# ir.net
KiCad netlist of a schematic drawn in EAGLE
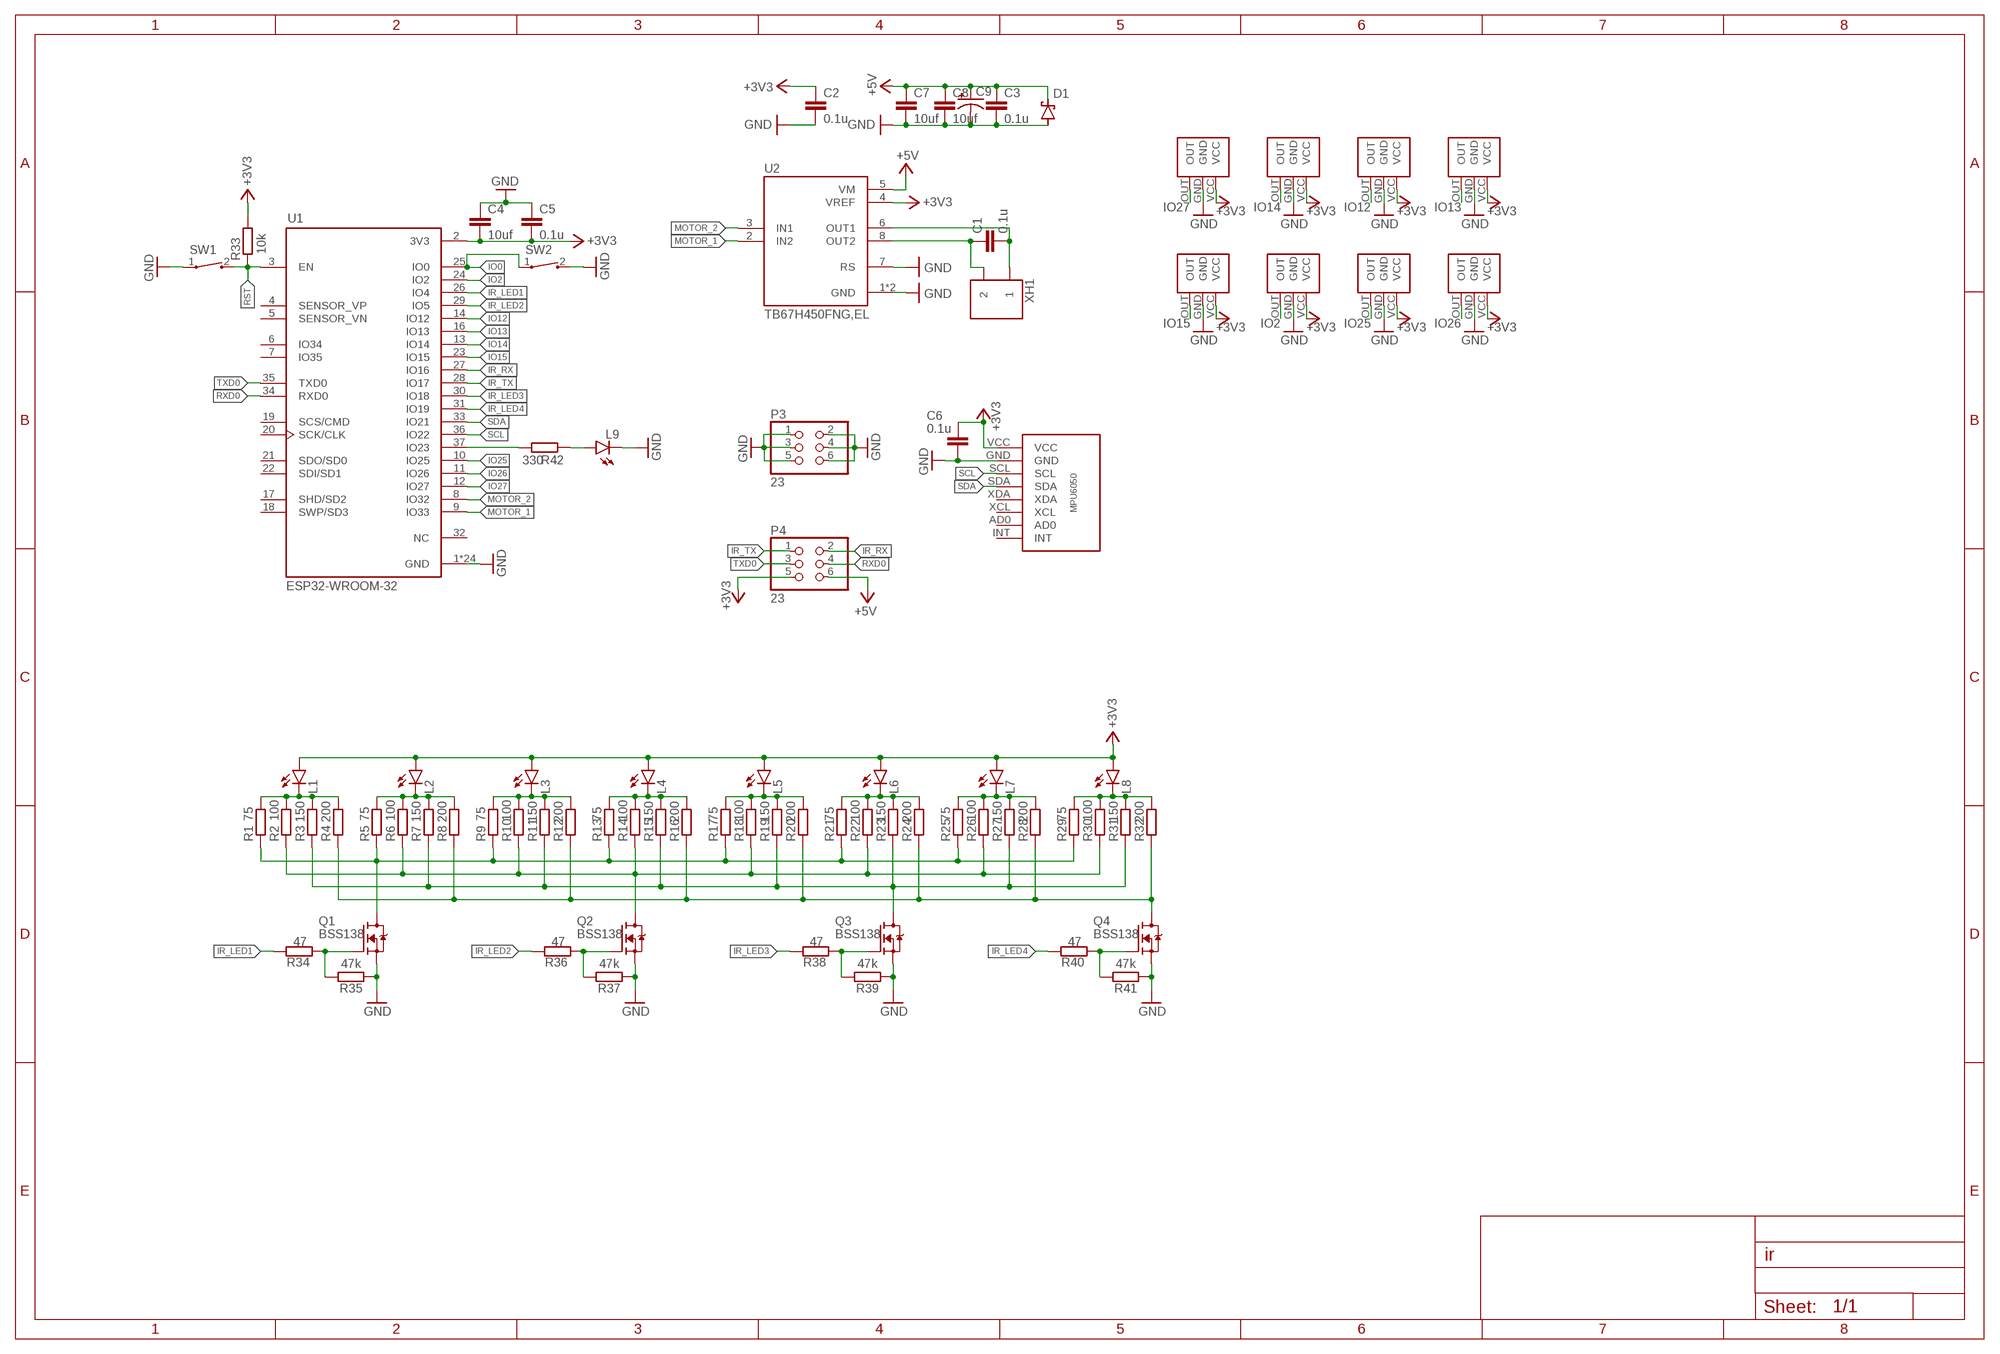
[diagram p0: schematic, sheet 1]

(export (version "E")
  (design (tool "Eeschema 10.0.6"))
  (components
    (comp (ref "C1")
      (value "0.1u")
      (footprint "eagle-import:C0603")
      (libsource (lib "eagle-import") (part "C-EUC0603"))
    )
    (comp (ref "C2")
      (value "0.1u")
      (footprint "eagle-import:C0603")
      (libsource (lib "eagle-import") (part "C-EUC0603"))
    )
    (comp (ref "C3")
      (value "0.1u")
      (footprint "eagle-import:C0603")
      (libsource (lib "eagle-import") (part "C-EUC0603"))
    )
    (comp (ref "C4")
      (value "10uf")
      (footprint "eagle-import:C0805")
      (libsource (lib "eagle-import") (part "C-EUC0805"))
    )
    (comp (ref "C5")
      (value "0.1u")
      (footprint "eagle-import:C0603")
      (libsource (lib "eagle-import") (part "C-EUC0603"))
    )
    (comp (ref "C6")
      (value "0.1u")
      (footprint "eagle-import:C0603")
      (libsource (lib "eagle-import") (part "C-EUC0603"))
    )
    (comp (ref "C7")
      (value "10uf")
      (footprint "eagle-import:C0805")
      (libsource (lib "eagle-import") (part "C-EUC0805"))
    )
    (comp (ref "C8")
      (value "10uf")
      (footprint "eagle-import:C0805")
      (libsource (lib "eagle-import") (part "C-EUC0805"))
    )
    (comp (ref "C9")
      (value "MH5")
      (footprint "eagle-import:MH5")
      (libsource (lib "eagle-import") (part "MH5"))
    )
    (comp (ref "D1")
      (value "SS2040FL")
      (footprint "eagle-import:SOD123FL")
      (libsource (lib "eagle-import") (part "SS2040FL"))
    )
    (comp (ref "IR1")
      (value "TSSP4038")
      (footprint "eagle-import:TSSP4038")
      (libsource (lib "eagle-import") (part "TSSP4038"))
    )
    (comp (ref "IR2")
      (value "TSSP4038")
      (footprint "eagle-import:TSSP4038")
      (libsource (lib "eagle-import") (part "TSSP4038"))
    )
    (comp (ref "IR3")
      (value "TSSP4038")
      (footprint "eagle-import:TSSP4038")
      (libsource (lib "eagle-import") (part "TSSP4038"))
    )
    (comp (ref "IR4")
      (value "TSSP4038")
      (footprint "eagle-import:TSSP4038")
      (libsource (lib "eagle-import") (part "TSSP4038"))
    )
    (comp (ref "IR5")
      (value "TSSP4038")
      (footprint "eagle-import:TSSP4038")
      (libsource (lib "eagle-import") (part "TSSP4038"))
    )
    (comp (ref "IR6")
      (value "TSSP4038")
      (footprint "eagle-import:TSSP4038")
      (libsource (lib "eagle-import") (part "TSSP4038"))
    )
    (comp (ref "IR7")
      (value "TSSP4038")
      (footprint "eagle-import:TSSP4038")
      (libsource (lib "eagle-import") (part "TSSP4038"))
    )
    (comp (ref "IR8")
      (value "TSSP4038")
      (footprint "eagle-import:TSSP4038")
      (libsource (lib "eagle-import") (part "TSSP4038"))
    )
    (comp (ref "L1")
      (value "LED")
      (footprint "eagle-import:LED")
      (libsource (lib "eagle-import") (part "LED"))
    )
    (comp (ref "L2")
      (value "LED")
      (footprint "eagle-import:LED")
      (libsource (lib "eagle-import") (part "LED"))
    )
    (comp (ref "L3")
      (value "LED")
      (footprint "eagle-import:LED")
      (libsource (lib "eagle-import") (part "LED"))
    )
    (comp (ref "L4")
      (value "LED")
      (footprint "eagle-import:LED")
      (libsource (lib "eagle-import") (part "LED"))
    )
    (comp (ref "L5")
      (value "LED")
      (footprint "eagle-import:LED")
      (libsource (lib "eagle-import") (part "LED"))
    )
    (comp (ref "L6")
      (value "LED")
      (footprint "eagle-import:LED")
      (libsource (lib "eagle-import") (part "LED"))
    )
    (comp (ref "L7")
      (value "LED")
      (footprint "eagle-import:LED")
      (libsource (lib "eagle-import") (part "LED"))
    )
    (comp (ref "L8")
      (value "LED")
      (footprint "eagle-import:LED")
      (libsource (lib "eagle-import") (part "LED"))
    )
    (comp (ref "L9")
      (value "SML-E12P8WT86")
      (footprint "eagle-import:LED_SML-LXFM0603SIC-TR")
      (libsource (lib "eagle-import") (part "SML-E12P8WT86"))
    )
    (comp (ref "P3") (value "23") (footprint "eagle-import:2_3") (libsource (lib "eagle-import") (part "23")))
    (comp (ref "P4") (value "23") (footprint "eagle-import:2_3") (libsource (lib "eagle-import") (part "23")))
    (comp (ref "Q1")
      (value "BSS138")
      (footprint "eagle-import:SOT95P240X111-3N")
      (fields (field (name "MF") "onsemi"))
      (libsource (lib "eagle-import") (part "BSS138"))
    )
    (comp (ref "Q2")
      (value "BSS138")
      (footprint "eagle-import:SOT95P240X111-3N")
      (fields (field (name "MF") "onsemi"))
      (libsource (lib "eagle-import") (part "BSS138"))
    )
    (comp (ref "Q3")
      (value "BSS138")
      (footprint "eagle-import:SOT95P240X111-3N")
      (fields (field (name "MF") "onsemi"))
      (libsource (lib "eagle-import") (part "BSS138"))
    )
    (comp (ref "Q4")
      (value "BSS138")
      (footprint "eagle-import:SOT95P240X111-3N")
      (fields (field (name "MF") "onsemi"))
      (libsource (lib "eagle-import") (part "BSS138"))
    )
    (comp (ref "R1")
      (value "75")
      (footprint "eagle-import:R0603")
      (libsource (lib "eagle-import") (part "R-EU_R0603"))
    )
    (comp (ref "R2")
      (value "100")
      (footprint "eagle-import:R0603")
      (libsource (lib "eagle-import") (part "R-EU_R0603"))
    )
    (comp (ref "R3")
      (value "150")
      (footprint "eagle-import:R0603")
      (libsource (lib "eagle-import") (part "R-EU_R0603"))
    )
    (comp (ref "R4")
      (value "200")
      (footprint "eagle-import:R0603")
      (libsource (lib "eagle-import") (part "R-EU_R0603"))
    )
    (comp (ref "R5")
      (value "75")
      (footprint "eagle-import:R0603")
      (libsource (lib "eagle-import") (part "R-EU_R0603"))
    )
    (comp (ref "R6")
      (value "100")
      (footprint "eagle-import:R0603")
      (libsource (lib "eagle-import") (part "R-EU_R0603"))
    )
    (comp (ref "R7")
      (value "150")
      (footprint "eagle-import:R0603")
      (libsource (lib "eagle-import") (part "R-EU_R0603"))
    )
    (comp (ref "R8")
      (value "200")
      (footprint "eagle-import:R0603")
      (libsource (lib "eagle-import") (part "R-EU_R0603"))
    )
    (comp (ref "R9")
      (value "75")
      (footprint "eagle-import:R0603")
      (libsource (lib "eagle-import") (part "R-EU_R0603"))
    )
    (comp (ref "R10")
      (value "100")
      (footprint "eagle-import:R0603")
      (libsource (lib "eagle-import") (part "R-EU_R0603"))
    )
    (comp (ref "R11")
      (value "150")
      (footprint "eagle-import:R0603")
      (libsource (lib "eagle-import") (part "R-EU_R0603"))
    )
    (comp (ref "R12")
      (value "200")
      (footprint "eagle-import:R0603")
      (libsource (lib "eagle-import") (part "R-EU_R0603"))
    )
    (comp (ref "R13")
      (value "75")
      (footprint "eagle-import:R0603")
      (libsource (lib "eagle-import") (part "R-EU_R0603"))
    )
    (comp (ref "R14")
      (value "100")
      (footprint "eagle-import:R0603")
      (libsource (lib "eagle-import") (part "R-EU_R0603"))
    )
    (comp (ref "R15")
      (value "150")
      (footprint "eagle-import:R0603")
      (libsource (lib "eagle-import") (part "R-EU_R0603"))
    )
    (comp (ref "R16")
      (value "200")
      (footprint "eagle-import:R0603")
      (libsource (lib "eagle-import") (part "R-EU_R0603"))
    )
    (comp (ref "R17")
      (value "75")
      (footprint "eagle-import:R0603")
      (libsource (lib "eagle-import") (part "R-EU_R0603"))
    )
    (comp (ref "R18")
      (value "100")
      (footprint "eagle-import:R0603")
      (libsource (lib "eagle-import") (part "R-EU_R0603"))
    )
    (comp (ref "R19")
      (value "150")
      (footprint "eagle-import:R0603")
      (libsource (lib "eagle-import") (part "R-EU_R0603"))
    )
    (comp (ref "R20")
      (value "200")
      (footprint "eagle-import:R0603")
      (libsource (lib "eagle-import") (part "R-EU_R0603"))
    )
    (comp (ref "R21")
      (value "75")
      (footprint "eagle-import:R0603")
      (libsource (lib "eagle-import") (part "R-EU_R0603"))
    )
    (comp (ref "R22")
      (value "100")
      (footprint "eagle-import:R0603")
      (libsource (lib "eagle-import") (part "R-EU_R0603"))
    )
    (comp (ref "R23")
      (value "150")
      (footprint "eagle-import:R0603")
      (libsource (lib "eagle-import") (part "R-EU_R0603"))
    )
    (comp (ref "R24")
      (value "200")
      (footprint "eagle-import:R0603")
      (libsource (lib "eagle-import") (part "R-EU_R0603"))
    )
    (comp (ref "R25")
      (value "75")
      (footprint "eagle-import:R0603")
      (libsource (lib "eagle-import") (part "R-EU_R0603"))
    )
    (comp (ref "R26")
      (value "100")
      (footprint "eagle-import:R0603")
      (libsource (lib "eagle-import") (part "R-EU_R0603"))
    )
    (comp (ref "R27")
      (value "150")
      (footprint "eagle-import:R0603")
      (libsource (lib "eagle-import") (part "R-EU_R0603"))
    )
    (comp (ref "R28")
      (value "200")
      (footprint "eagle-import:R0603")
      (libsource (lib "eagle-import") (part "R-EU_R0603"))
    )
    (comp (ref "R29")
      (value "75")
      (footprint "eagle-import:R0603")
      (libsource (lib "eagle-import") (part "R-EU_R0603"))
    )
    (comp (ref "R30")
      (value "100")
      (footprint "eagle-import:R0603")
      (libsource (lib "eagle-import") (part "R-EU_R0603"))
    )
    (comp (ref "R31")
      (value "150")
      (footprint "eagle-import:R0603")
      (libsource (lib "eagle-import") (part "R-EU_R0603"))
    )
    (comp (ref "R32")
      (value "200")
      (footprint "eagle-import:R0603")
      (libsource (lib "eagle-import") (part "R-EU_R0603"))
    )
    (comp (ref "R33")
      (value "10k")
      (footprint "eagle-import:R0603")
      (libsource (lib "eagle-import") (part "R-EU_R0603"))
    )
    (comp (ref "R34")
      (value "47")
      (footprint "eagle-import:R0603")
      (libsource (lib "eagle-import") (part "R-EU_R0603"))
    )
    (comp (ref "R35")
      (value "47k")
      (footprint "eagle-import:R0603")
      (libsource (lib "eagle-import") (part "R-EU_R0603"))
    )
    (comp (ref "R36")
      (value "47")
      (footprint "eagle-import:R0603")
      (libsource (lib "eagle-import") (part "R-EU_R0603"))
    )
    (comp (ref "R37")
      (value "47k")
      (footprint "eagle-import:R0603")
      (libsource (lib "eagle-import") (part "R-EU_R0603"))
    )
    (comp (ref "R38")
      (value "47")
      (footprint "eagle-import:R0603")
      (libsource (lib "eagle-import") (part "R-EU_R0603"))
    )
    (comp (ref "R39")
      (value "47k")
      (footprint "eagle-import:R0603")
      (libsource (lib "eagle-import") (part "R-EU_R0603"))
    )
    (comp (ref "R40")
      (value "47")
      (footprint "eagle-import:R0603")
      (libsource (lib "eagle-import") (part "R-EU_R0603"))
    )
    (comp (ref "R41")
      (value "47k")
      (footprint "eagle-import:R0603")
      (libsource (lib "eagle-import") (part "R-EU_R0603"))
    )
    (comp (ref "R42")
      (value "330")
      (footprint "eagle-import:R0603")
      (libsource (lib "eagle-import") (part "R-EU_R0603"))
    )
    (comp (ref "SW1")
      (value "TATE")
      (footprint "eagle-import:TATE")
      (libsource (lib "eagle-import") (part "TATE"))
    )
    (comp (ref "SW2")
      (value "TATE")
      (footprint "eagle-import:TATE")
      (libsource (lib "eagle-import") (part "TATE"))
    )
    (comp (ref "U$1")
      (value "MPU6050")
      (footprint "eagle-import:MPU6050")
      (libsource (lib "eagle-import") (part "MPU6050"))
    )
    (comp (ref "U1")
      (value "ESP32-WROOM-32")
      (footprint "eagle-import:MODULE_ESP32-WROOM-32")
      (fields (field (name "MF") "Espressif Systems"))
      (libsource (lib "eagle-import") (part "ESP32-WROOM-32"))
    )
    (comp (ref "U2")
      (value "TB67H450FNG,EL")
      (footprint "eagle-import:SOIC127P599X175-9N")
      (fields (field (name "MF") "Toshiba Semiconductor and Storage"))
      (libsource (lib "eagle-import") (part "TB67H450FNG,EL"))
    )
    (comp (ref "XH1")
      (value "S2B")
      (footprint "eagle-import:S2B")
      (libsource (lib "eagle-import") (part "S2B"))
    )
  )
  (nets
    (net (code "1") (name "+3V3") (class "Default")
      (node (ref "C2") (pin "1") (pinfunction "1_1") (pintype "passive"))
      (node (ref "C4") (pin "2") (pinfunction "2_2") (pintype "passive"))
      (node (ref "C5") (pin "2") (pinfunction "2_2") (pintype "passive"))
      (node (ref "C6") (pin "1") (pinfunction "1_1") (pintype "passive"))
      (node (ref "IR1") (pin "VCC") (pinfunction "VCC_VCC") (pintype "bidirectional"))
      (node (ref "IR2") (pin "VCC") (pinfunction "VCC_VCC") (pintype "bidirectional"))
      (node (ref "IR3") (pin "VCC") (pinfunction "VCC_VCC") (pintype "bidirectional"))
      (node (ref "IR4") (pin "VCC") (pinfunction "VCC_VCC") (pintype "bidirectional"))
      (node (ref "IR5") (pin "VCC") (pinfunction "VCC_VCC") (pintype "bidirectional"))
      (node (ref "IR6") (pin "VCC") (pinfunction "VCC_VCC") (pintype "bidirectional"))
      (node (ref "IR7") (pin "VCC") (pinfunction "VCC_VCC") (pintype "bidirectional"))
      (node (ref "IR8") (pin "VCC") (pinfunction "VCC_VCC") (pintype "bidirectional"))
      (node (ref "L1") (pin "+") (pinfunction "+_+") (pintype "passive"))
      (node (ref "L2") (pin "+") (pinfunction "+_+") (pintype "passive"))
      (node (ref "L3") (pin "+") (pinfunction "+_+") (pintype "passive"))
      (node (ref "L4") (pin "+") (pinfunction "+_+") (pintype "passive"))
      (node (ref "L5") (pin "+") (pinfunction "+_+") (pintype "passive"))
      (node (ref "L6") (pin "+") (pinfunction "+_+") (pintype "passive"))
      (node (ref "L7") (pin "+") (pinfunction "+_+") (pintype "passive"))
      (node (ref "L8") (pin "+") (pinfunction "+_+") (pintype "passive"))
      (node (ref "P4") (pin "5") (pinfunction "5_5") (pintype "passive"))
      (node (ref "R33") (pin "2") (pinfunction "2_2") (pintype "passive"))
      (node (ref "U$1") (pin "VCC") (pinfunction "VCC_VCC") (pintype "bidirectional"))
      (node (ref "U1") (pin "2") (pinfunction "3V3_2") (pintype "power_in"))
      (node (ref "U2") (pin "4") (pinfunction "VREF_4") (pintype "power_in"))
    )
    (net (code "2") (name "+5V") (class "Default")
      (node (ref "C3") (pin "1") (pinfunction "1_1") (pintype "passive"))
      (node (ref "C7") (pin "1") (pinfunction "1_1") (pintype "passive"))
      (node (ref "C8") (pin "1") (pinfunction "1_1") (pintype "passive"))
      (node (ref "C9") (pin "+") (pinfunction "+_+") (pintype "passive"))
      (node (ref "D1") (pin "C") (pinfunction "C_C") (pintype "passive"))
      (node (ref "P4") (pin "6") (pinfunction "6_6") (pintype "passive"))
      (node (ref "U2") (pin "5") (pinfunction "VM_5") (pintype "power_in"))
    )
    (net (code "3") (name "GND") (class "Default")
      (node (ref "C2") (pin "2") (pinfunction "2_2") (pintype "passive"))
      (node (ref "C3") (pin "2") (pinfunction "2_2") (pintype "passive"))
      (node (ref "C4") (pin "1") (pinfunction "1_1") (pintype "passive"))
      (node (ref "C5") (pin "1") (pinfunction "1_1") (pintype "passive"))
      (node (ref "C6") (pin "2") (pinfunction "2_2") (pintype "passive"))
      (node (ref "C7") (pin "2") (pinfunction "2_2") (pintype "passive"))
      (node (ref "C8") (pin "2") (pinfunction "2_2") (pintype "passive"))
      (node (ref "C9") (pin "-") (pinfunction "-_-") (pintype "passive"))
      (node (ref "D1") (pin "A") (pinfunction "A_A") (pintype "passive"))
      (node (ref "IR1") (pin "GND") (pinfunction "GND_GND") (pintype "bidirectional"))
      (node (ref "IR2") (pin "GND") (pinfunction "GND_GND") (pintype "bidirectional"))
      (node (ref "IR3") (pin "GND") (pinfunction "GND_GND") (pintype "bidirectional"))
      (node (ref "IR4") (pin "GND") (pinfunction "GND_GND") (pintype "bidirectional"))
      (node (ref "IR5") (pin "GND") (pinfunction "GND_GND") (pintype "bidirectional"))
      (node (ref "IR6") (pin "GND") (pinfunction "GND_GND") (pintype "bidirectional"))
      (node (ref "IR7") (pin "GND") (pinfunction "GND_GND") (pintype "bidirectional"))
      (node (ref "IR8") (pin "GND") (pinfunction "GND_GND") (pintype "bidirectional"))
      (node (ref "L9") (pin "C") (pinfunction "C_C") (pintype "passive"))
      (node (ref "P3") (pin "1") (pinfunction "1_1") (pintype "passive"))
      (node (ref "P3") (pin "2") (pinfunction "2_2") (pintype "passive"))
      (node (ref "P3") (pin "3") (pinfunction "3_3") (pintype "passive"))
      (node (ref "P3") (pin "4") (pinfunction "4_4") (pintype "passive"))
      (node (ref "P3") (pin "5") (pinfunction "5_5") (pintype "passive"))
      (node (ref "P3") (pin "6") (pinfunction "6_6") (pintype "passive"))
      (node (ref "Q1") (pin "2") (pinfunction "S_2") (pintype "passive"))
      (node (ref "Q2") (pin "2") (pinfunction "S_2") (pintype "passive"))
      (node (ref "Q3") (pin "2") (pinfunction "S_2") (pintype "passive"))
      (node (ref "Q4") (pin "2") (pinfunction "S_2") (pintype "passive"))
      (node (ref "R35") (pin "2") (pinfunction "2_2") (pintype "passive"))
      (node (ref "R37") (pin "2") (pinfunction "2_2") (pintype "passive"))
      (node (ref "R39") (pin "2") (pinfunction "2_2") (pintype "passive"))
      (node (ref "R41") (pin "2") (pinfunction "2_2") (pintype "passive"))
      (node (ref "SW1") (pin "1") (pinfunction "1_1") (pintype "passive"))
      (node (ref "SW2") (pin "2") (pinfunction "2_2") (pintype "passive"))
      (node (ref "U$1") (pin "GND") (pinfunction "GND_GND") (pintype "bidirectional"))
      (node (ref "U1") (pin "1") (pinfunction "GND_1") (pintype "power_in"))
      (node (ref "U1") (pin "15") (pinfunction "GND_15") (pintype "power_in"))
      (node (ref "U1") (pin "38") (pinfunction "GND_38") (pintype "power_in"))
      (node (ref "U1") (pin "39_1") (pinfunction "GND_39_1") (pintype "power_in"))
      (node (ref "U1") (pin "39_10") (pinfunction "GND_39_10") (pintype "power_in"))
      (node (ref "U1") (pin "39_11") (pinfunction "GND_39_11") (pintype "power_in"))
      (node (ref "U1") (pin "39_12") (pinfunction "GND_39_12") (pintype "power_in"))
      (node (ref "U1") (pin "39_13") (pinfunction "GND_39_13") (pintype "power_in"))
      (node (ref "U1") (pin "39_14") (pinfunction "GND_39_14") (pintype "power_in"))
      (node (ref "U1") (pin "39_15") (pinfunction "GND_39_15") (pintype "power_in"))
      (node (ref "U1") (pin "39_16") (pinfunction "GND_39_16") (pintype "power_in"))
      (node (ref "U1") (pin "39_17") (pinfunction "GND_39_17") (pintype "power_in"))
      (node (ref "U1") (pin "39_18") (pinfunction "GND_39_18") (pintype "power_in"))
      (node (ref "U1") (pin "39_19") (pinfunction "GND_39_19") (pintype "power_in"))
      (node (ref "U1") (pin "39_2") (pinfunction "GND_39_2") (pintype "power_in"))
      (node (ref "U1") (pin "39_20") (pinfunction "GND_39_20") (pintype "power_in"))
      (node (ref "U1") (pin "39_21") (pinfunction "GND_39_21") (pintype "power_in"))
      (node (ref "U1") (pin "39_3") (pinfunction "GND_39_3") (pintype "power_in"))
      (node (ref "U1") (pin "39_4") (pinfunction "GND_39_4") (pintype "power_in"))
      (node (ref "U1") (pin "39_5") (pinfunction "GND_39_5") (pintype "power_in"))
      (node (ref "U1") (pin "39_6") (pinfunction "GND_39_6") (pintype "power_in"))
      (node (ref "U1") (pin "39_7") (pinfunction "GND_39_7") (pintype "power_in"))
      (node (ref "U1") (pin "39_8") (pinfunction "GND_39_8") (pintype "power_in"))
      (node (ref "U1") (pin "39_9") (pinfunction "GND_39_9") (pintype "power_in"))
      (node (ref "U2") (pin "1") (pinfunction "GND_1") (pintype "power_in"))
      (node (ref "U2") (pin "7") (pinfunction "RS_7") (pintype "output"))
      (node (ref "U2") (pin "9") (pinfunction "GND_9") (pintype "power_in"))
    )
    (net (code "4") (name "IO0") (class "Default")
      (node (ref "SW2") (pin "1") (pinfunction "1_1") (pintype "passive"))
      (node (ref "U1") (pin "25") (pinfunction "IO0_25") (pintype "bidirectional"))
    )
    (net (code "5") (name "IO2") (class "Default")
      (node (ref "IR6") (pin "OUT") (pinfunction "OUT_OUT") (pintype "bidirectional"))
      (node (ref "U1") (pin "24") (pinfunction "IO2_24") (pintype "bidirectional"))
    )
    (net (code "6") (name "IO12") (class "Default")
      (node (ref "IR3") (pin "OUT") (pinfunction "OUT_OUT") (pintype "bidirectional"))
      (node (ref "U1") (pin "14") (pinfunction "IO12_14") (pintype "bidirectional"))
    )
    (net (code "7") (name "IO13") (class "Default")
      (node (ref "IR4") (pin "OUT") (pinfunction "OUT_OUT") (pintype "bidirectional"))
      (node (ref "U1") (pin "16") (pinfunction "IO13_16") (pintype "bidirectional"))
    )
    (net (code "8") (name "IO14") (class "Default")
      (node (ref "IR2") (pin "OUT") (pinfunction "OUT_OUT") (pintype "bidirectional"))
      (node (ref "U1") (pin "13") (pinfunction "IO14_13") (pintype "bidirectional"))
    )
    (net (code "9") (name "IO15") (class "Default")
      (node (ref "IR5") (pin "OUT") (pinfunction "OUT_OUT") (pintype "bidirectional"))
      (node (ref "U1") (pin "23") (pinfunction "IO15_23") (pintype "bidirectional"))
    )
    (net (code "10") (name "IO25") (class "Default")
      (node (ref "IR7") (pin "OUT") (pinfunction "OUT_OUT") (pintype "bidirectional"))
      (node (ref "U1") (pin "10") (pinfunction "IO25_10") (pintype "bidirectional"))
    )
    (net (code "11") (name "IO26") (class "Default")
      (node (ref "IR8") (pin "OUT") (pinfunction "OUT_OUT") (pintype "bidirectional"))
      (node (ref "U1") (pin "11") (pinfunction "IO26_11") (pintype "bidirectional"))
    )
    (net (code "12") (name "IO27") (class "Default")
      (node (ref "IR1") (pin "OUT") (pinfunction "OUT_OUT") (pintype "bidirectional"))
      (node (ref "U1") (pin "12") (pinfunction "IO27_12") (pintype "bidirectional"))
    )
    (net (code "13") (name "IR_LED1") (class "Default")
      (node (ref "R34") (pin "2") (pinfunction "2_2") (pintype "passive"))
      (node (ref "U1") (pin "26") (pinfunction "IO4_26") (pintype "bidirectional"))
    )
    (net (code "14") (name "IR_LED2") (class "Default")
      (node (ref "R36") (pin "2") (pinfunction "2_2") (pintype "passive"))
      (node (ref "U1") (pin "29") (pinfunction "IO5_29") (pintype "bidirectional"))
    )
    (net (code "15") (name "IR_LED3") (class "Default")
      (node (ref "R38") (pin "2") (pinfunction "2_2") (pintype "passive"))
      (node (ref "U1") (pin "30") (pinfunction "IO18_30") (pintype "bidirectional"))
    )
    (net (code "16") (name "IR_LED4") (class "Default")
      (node (ref "R40") (pin "2") (pinfunction "2_2") (pintype "passive"))
      (node (ref "U1") (pin "31") (pinfunction "IO19_31") (pintype "bidirectional"))
    )
    (net (code "17") (name "IR_RX") (class "Default")
      (node (ref "P4") (pin "2") (pinfunction "2_2") (pintype "passive"))
      (node (ref "U1") (pin "27") (pinfunction "IO16_27") (pintype "bidirectional"))
    )
    (net (code "18") (name "IR_TX") (class "Default")
      (node (ref "P4") (pin "1") (pinfunction "1_1") (pintype "passive"))
      (node (ref "U1") (pin "28") (pinfunction "IO17_28") (pintype "bidirectional"))
    )
    (net (code "19") (name "MOTOR_1") (class "Default")
      (node (ref "U1") (pin "9") (pinfunction "IO33_9") (pintype "bidirectional"))
      (node (ref "U2") (pin "2") (pinfunction "IN2_2") (pintype "input"))
    )
    (net (code "20") (name "MOTOR_2") (class "Default")
      (node (ref "U1") (pin "8") (pinfunction "IO32_8") (pintype "bidirectional"))
      (node (ref "U2") (pin "3") (pinfunction "IN1_3") (pintype "input"))
    )
    (net (code "21") (name "Net-(L1-Pad-)") (class "Default")
      (node (ref "L1") (pin "-") (pinfunction "-_-") (pintype "passive"))
      (node (ref "R1") (pin "2") (pinfunction "2_2") (pintype "passive"))
      (node (ref "R2") (pin "2") (pinfunction "2_2") (pintype "passive"))
      (node (ref "R3") (pin "2") (pinfunction "2_2") (pintype "passive"))
      (node (ref "R4") (pin "2") (pinfunction "2_2") (pintype "passive"))
    )
    (net (code "22") (name "Net-(L2-Pad-)") (class "Default")
      (node (ref "L2") (pin "-") (pinfunction "-_-") (pintype "passive"))
      (node (ref "R5") (pin "2") (pinfunction "2_2") (pintype "passive"))
      (node (ref "R6") (pin "2") (pinfunction "2_2") (pintype "passive"))
      (node (ref "R7") (pin "2") (pinfunction "2_2") (pintype "passive"))
      (node (ref "R8") (pin "2") (pinfunction "2_2") (pintype "passive"))
    )
    (net (code "23") (name "Net-(L3-Pad-)") (class "Default")
      (node (ref "L3") (pin "-") (pinfunction "-_-") (pintype "passive"))
      (node (ref "R10") (pin "2") (pinfunction "2_2") (pintype "passive"))
      (node (ref "R11") (pin "2") (pinfunction "2_2") (pintype "passive"))
      (node (ref "R12") (pin "2") (pinfunction "2_2") (pintype "passive"))
      (node (ref "R9") (pin "2") (pinfunction "2_2") (pintype "passive"))
    )
    (net (code "24") (name "Net-(L4-Pad-)") (class "Default")
      (node (ref "L4") (pin "-") (pinfunction "-_-") (pintype "passive"))
      (node (ref "R13") (pin "2") (pinfunction "2_2") (pintype "passive"))
      (node (ref "R14") (pin "2") (pinfunction "2_2") (pintype "passive"))
      (node (ref "R15") (pin "2") (pinfunction "2_2") (pintype "passive"))
      (node (ref "R16") (pin "2") (pinfunction "2_2") (pintype "passive"))
    )
    (net (code "25") (name "Net-(L5-Pad-)") (class "Default")
      (node (ref "L5") (pin "-") (pinfunction "-_-") (pintype "passive"))
      (node (ref "R17") (pin "2") (pinfunction "2_2") (pintype "passive"))
      (node (ref "R18") (pin "2") (pinfunction "2_2") (pintype "passive"))
      (node (ref "R19") (pin "2") (pinfunction "2_2") (pintype "passive"))
      (node (ref "R20") (pin "2") (pinfunction "2_2") (pintype "passive"))
    )
    (net (code "26") (name "Net-(L6-Pad-)") (class "Default")
      (node (ref "L6") (pin "-") (pinfunction "-_-") (pintype "passive"))
      (node (ref "R21") (pin "2") (pinfunction "2_2") (pintype "passive"))
      (node (ref "R22") (pin "2") (pinfunction "2_2") (pintype "passive"))
      (node (ref "R23") (pin "2") (pinfunction "2_2") (pintype "passive"))
      (node (ref "R24") (pin "2") (pinfunction "2_2") (pintype "passive"))
    )
    (net (code "27") (name "Net-(L7-Pad-)") (class "Default")
      (node (ref "L7") (pin "-") (pinfunction "-_-") (pintype "passive"))
      (node (ref "R25") (pin "2") (pinfunction "2_2") (pintype "passive"))
      (node (ref "R26") (pin "2") (pinfunction "2_2") (pintype "passive"))
      (node (ref "R27") (pin "2") (pinfunction "2_2") (pintype "passive"))
      (node (ref "R28") (pin "2") (pinfunction "2_2") (pintype "passive"))
    )
    (net (code "28") (name "Net-(L8-Pad-)") (class "Default")
      (node (ref "L8") (pin "-") (pinfunction "-_-") (pintype "passive"))
      (node (ref "R29") (pin "2") (pinfunction "2_2") (pintype "passive"))
      (node (ref "R30") (pin "2") (pinfunction "2_2") (pintype "passive"))
      (node (ref "R31") (pin "2") (pinfunction "2_2") (pintype "passive"))
      (node (ref "R32") (pin "2") (pinfunction "2_2") (pintype "passive"))
    )
    (net (code "29") (name "Net-(L9-PadA)") (class "Default")
      (node (ref "L9") (pin "A") (pinfunction "A_A") (pintype "passive"))
      (node (ref "R42") (pin "1") (pinfunction "1_1") (pintype "passive"))
    )
    (net (code "30") (name "Net-(Q1-D)") (class "Default")
      (node (ref "Q1") (pin "3") (pinfunction "D_3") (pintype "passive"))
      (node (ref "R1") (pin "1") (pinfunction "1_1") (pintype "passive"))
      (node (ref "R13") (pin "1") (pinfunction "1_1") (pintype "passive"))
      (node (ref "R17") (pin "1") (pinfunction "1_1") (pintype "passive"))
      (node (ref "R21") (pin "1") (pinfunction "1_1") (pintype "passive"))
      (node (ref "R25") (pin "1") (pinfunction "1_1") (pintype "passive"))
      (node (ref "R29") (pin "1") (pinfunction "1_1") (pintype "passive"))
      (node (ref "R5") (pin "1") (pinfunction "1_1") (pintype "passive"))
      (node (ref "R9") (pin "1") (pinfunction "1_1") (pintype "passive"))
    )
    (net (code "31") (name "Net-(Q1-G)") (class "Default")
      (node (ref "Q1") (pin "1") (pinfunction "G_1") (pintype "passive"))
      (node (ref "R34") (pin "1") (pinfunction "1_1") (pintype "passive"))
      (node (ref "R35") (pin "1") (pinfunction "1_1") (pintype "passive"))
    )
    (net (code "32") (name "Net-(Q2-D)") (class "Default")
      (node (ref "Q2") (pin "3") (pinfunction "D_3") (pintype "passive"))
      (node (ref "R10") (pin "1") (pinfunction "1_1") (pintype "passive"))
      (node (ref "R14") (pin "1") (pinfunction "1_1") (pintype "passive"))
      (node (ref "R18") (pin "1") (pinfunction "1_1") (pintype "passive"))
      (node (ref "R2") (pin "1") (pinfunction "1_1") (pintype "passive"))
      (node (ref "R22") (pin "1") (pinfunction "1_1") (pintype "passive"))
      (node (ref "R26") (pin "1") (pinfunction "1_1") (pintype "passive"))
      (node (ref "R30") (pin "1") (pinfunction "1_1") (pintype "passive"))
      (node (ref "R6") (pin "1") (pinfunction "1_1") (pintype "passive"))
    )
    (net (code "33") (name "Net-(Q2-G)") (class "Default")
      (node (ref "Q2") (pin "1") (pinfunction "G_1") (pintype "passive"))
      (node (ref "R36") (pin "1") (pinfunction "1_1") (pintype "passive"))
      (node (ref "R37") (pin "1") (pinfunction "1_1") (pintype "passive"))
    )
    (net (code "34") (name "Net-(Q3-D)") (class "Default")
      (node (ref "Q3") (pin "3") (pinfunction "D_3") (pintype "passive"))
      (node (ref "R11") (pin "1") (pinfunction "1_1") (pintype "passive"))
      (node (ref "R15") (pin "1") (pinfunction "1_1") (pintype "passive"))
      (node (ref "R19") (pin "1") (pinfunction "1_1") (pintype "passive"))
      (node (ref "R23") (pin "1") (pinfunction "1_1") (pintype "passive"))
      (node (ref "R27") (pin "1") (pinfunction "1_1") (pintype "passive"))
      (node (ref "R3") (pin "1") (pinfunction "1_1") (pintype "passive"))
      (node (ref "R31") (pin "1") (pinfunction "1_1") (pintype "passive"))
      (node (ref "R7") (pin "1") (pinfunction "1_1") (pintype "passive"))
    )
    (net (code "35") (name "Net-(Q3-G)") (class "Default")
      (node (ref "Q3") (pin "1") (pinfunction "G_1") (pintype "passive"))
      (node (ref "R38") (pin "1") (pinfunction "1_1") (pintype "passive"))
      (node (ref "R39") (pin "1") (pinfunction "1_1") (pintype "passive"))
    )
    (net (code "36") (name "Net-(Q4-D)") (class "Default")
      (node (ref "Q4") (pin "3") (pinfunction "D_3") (pintype "passive"))
      (node (ref "R12") (pin "1") (pinfunction "1_1") (pintype "passive"))
      (node (ref "R16") (pin "1") (pinfunction "1_1") (pintype "passive"))
      (node (ref "R20") (pin "1") (pinfunction "1_1") (pintype "passive"))
      (node (ref "R24") (pin "1") (pinfunction "1_1") (pintype "passive"))
      (node (ref "R28") (pin "1") (pinfunction "1_1") (pintype "passive"))
      (node (ref "R32") (pin "1") (pinfunction "1_1") (pintype "passive"))
      (node (ref "R4") (pin "1") (pinfunction "1_1") (pintype "passive"))
      (node (ref "R8") (pin "1") (pinfunction "1_1") (pintype "passive"))
    )
    (net (code "37") (name "Net-(Q4-G)") (class "Default")
      (node (ref "Q4") (pin "1") (pinfunction "G_1") (pintype "passive"))
      (node (ref "R40") (pin "1") (pinfunction "1_1") (pintype "passive"))
      (node (ref "R41") (pin "1") (pinfunction "1_1") (pintype "passive"))
    )
    (net (code "38") (name "Net-(U1-IO23)") (class "Default")
      (node (ref "R42") (pin "2") (pinfunction "2_2") (pintype "passive"))
      (node (ref "U1") (pin "37") (pinfunction "IO23_37") (pintype "bidirectional"))
    )
    (net (code "39") (name "Net-(U2-OUT1)") (class "Default")
      (node (ref "C1") (pin "2") (pinfunction "2_2") (pintype "passive"))
      (node (ref "U2") (pin "6") (pinfunction "OUT1_6") (pintype "output"))
      (node (ref "XH1") (pin "1") (pinfunction "1_1") (pintype "bidirectional"))
    )
    (net (code "40") (name "Net-(U2-OUT2)") (class "Default")
      (node (ref "C1") (pin "1") (pinfunction "1_1") (pintype "passive"))
      (node (ref "U2") (pin "8") (pinfunction "OUT2_8") (pintype "output"))
      (node (ref "XH1") (pin "2") (pinfunction "2_2") (pintype "bidirectional"))
    )
    (net (code "41") (name "RST") (class "Default")
      (node (ref "R33") (pin "1") (pinfunction "1_1") (pintype "passive"))
      (node (ref "SW1") (pin "2") (pinfunction "2_2") (pintype "passive"))
      (node (ref "U1") (pin "3") (pinfunction "EN_3") (pintype "input"))
    )
    (net (code "42") (name "RXD0") (class "Default")
      (node (ref "P4") (pin "4") (pinfunction "4_4") (pintype "passive"))
      (node (ref "U1") (pin "34") (pinfunction "RXD0_34") (pintype "bidirectional"))
    )
    (net (code "43") (name "SCL") (class "Default")
      (node (ref "U$1") (pin "SCL") (pinfunction "SCL_SCL") (pintype "bidirectional"))
      (node (ref "U1") (pin "36") (pinfunction "IO22_36") (pintype "bidirectional"))
    )
    (net (code "44") (name "SDA") (class "Default")
      (node (ref "U$1") (pin "SDA") (pinfunction "SDA_SDA") (pintype "bidirectional"))
      (node (ref "U1") (pin "33") (pinfunction "IO21_33") (pintype "bidirectional"))
    )
    (net (code "45") (name "TXD0") (class "Default")
      (node (ref "P4") (pin "3") (pinfunction "3_3") (pintype "passive"))
      (node (ref "U1") (pin "35") (pinfunction "TXD0_35") (pintype "bidirectional"))
    )
    (net (code "46") (name "unconnected-(U$1-PadAD0)") (class "Default")
      (node (ref "U$1") (pin "AD0") (pinfunction "AD0_AD0") (pintype "bidirectional"))
    )
    (net (code "47") (name "unconnected-(U$1-PadINT)") (class "Default")
      (node (ref "U$1") (pin "INT") (pinfunction "INT_INT") (pintype "bidirectional"))
    )
    (net (code "48") (name "unconnected-(U$1-PadXCL)") (class "Default")
      (node (ref "U$1") (pin "XCL") (pinfunction "XCL_XCL") (pintype "bidirectional"))
    )
    (net (code "49") (name "unconnected-(U$1-PadXDA)") (class "Default")
      (node (ref "U$1") (pin "XDA") (pinfunction "XDA_XDA") (pintype "bidirectional"))
    )
    (net (code "50") (name "unconnected-(U1-IO34-Pad6)") (class "Default")
      (node (ref "U1") (pin "6") (pinfunction "IO34_6") (pintype "input"))
    )
    (net (code "51") (name "unconnected-(U1-IO35-Pad7)") (class "Default")
      (node (ref "U1") (pin "7") (pinfunction "IO35_7") (pintype "input"))
    )
    (net (code "52") (name "unconnected-(U1-NC-Pad32)") (class "Default")
      (node (ref "U1") (pin "32") (pinfunction "NC_32") (pintype "no_connect"))
    )
    (net (code "53") (name "unconnected-(U1-SCK{slash}CLK-Pad20)") (class "Default")
      (node (ref "U1") (pin "20") (pinfunction "SCK/CLK_20") (pintype "bidirectional"))
    )
    (net (code "54") (name "unconnected-(U1-SCS{slash}CMD-Pad19)") (class "Default")
      (node (ref "U1") (pin "19") (pinfunction "SCS/CMD_19") (pintype "bidirectional"))
    )
    (net (code "55") (name "unconnected-(U1-SDI{slash}SD1-Pad22)") (class "Default")
      (node (ref "U1") (pin "22") (pinfunction "SDI/SD1_22") (pintype "bidirectional"))
    )
    (net (code "56") (name "unconnected-(U1-SDO{slash}SD0-Pad21)") (class "Default")
      (node (ref "U1") (pin "21") (pinfunction "SDO/SD0_21") (pintype "bidirectional"))
    )
    (net (code "57") (name "unconnected-(U1-SENSOR_VN-Pad5)") (class "Default")
      (node (ref "U1") (pin "5") (pinfunction "SENSOR_VN_5") (pintype "input"))
    )
    (net (code "58") (name "unconnected-(U1-SENSOR_VP-Pad4)") (class "Default")
      (node (ref "U1") (pin "4") (pinfunction "SENSOR_VP_4") (pintype "input"))
    )
    (net (code "59") (name "unconnected-(U1-SHD{slash}SD2-Pad17)") (class "Default")
      (node (ref "U1") (pin "17") (pinfunction "SHD/SD2_17") (pintype "bidirectional"))
    )
    (net (code "60") (name "unconnected-(U1-SWP{slash}SD3-Pad18)") (class "Default")
      (node (ref "U1") (pin "18") (pinfunction "SWP/SD3_18") (pintype "bidirectional"))
    )
  )
)
